# LEDboard_v0_2-R001.net
KiCad netlist of a schematic drawn in EAGLE
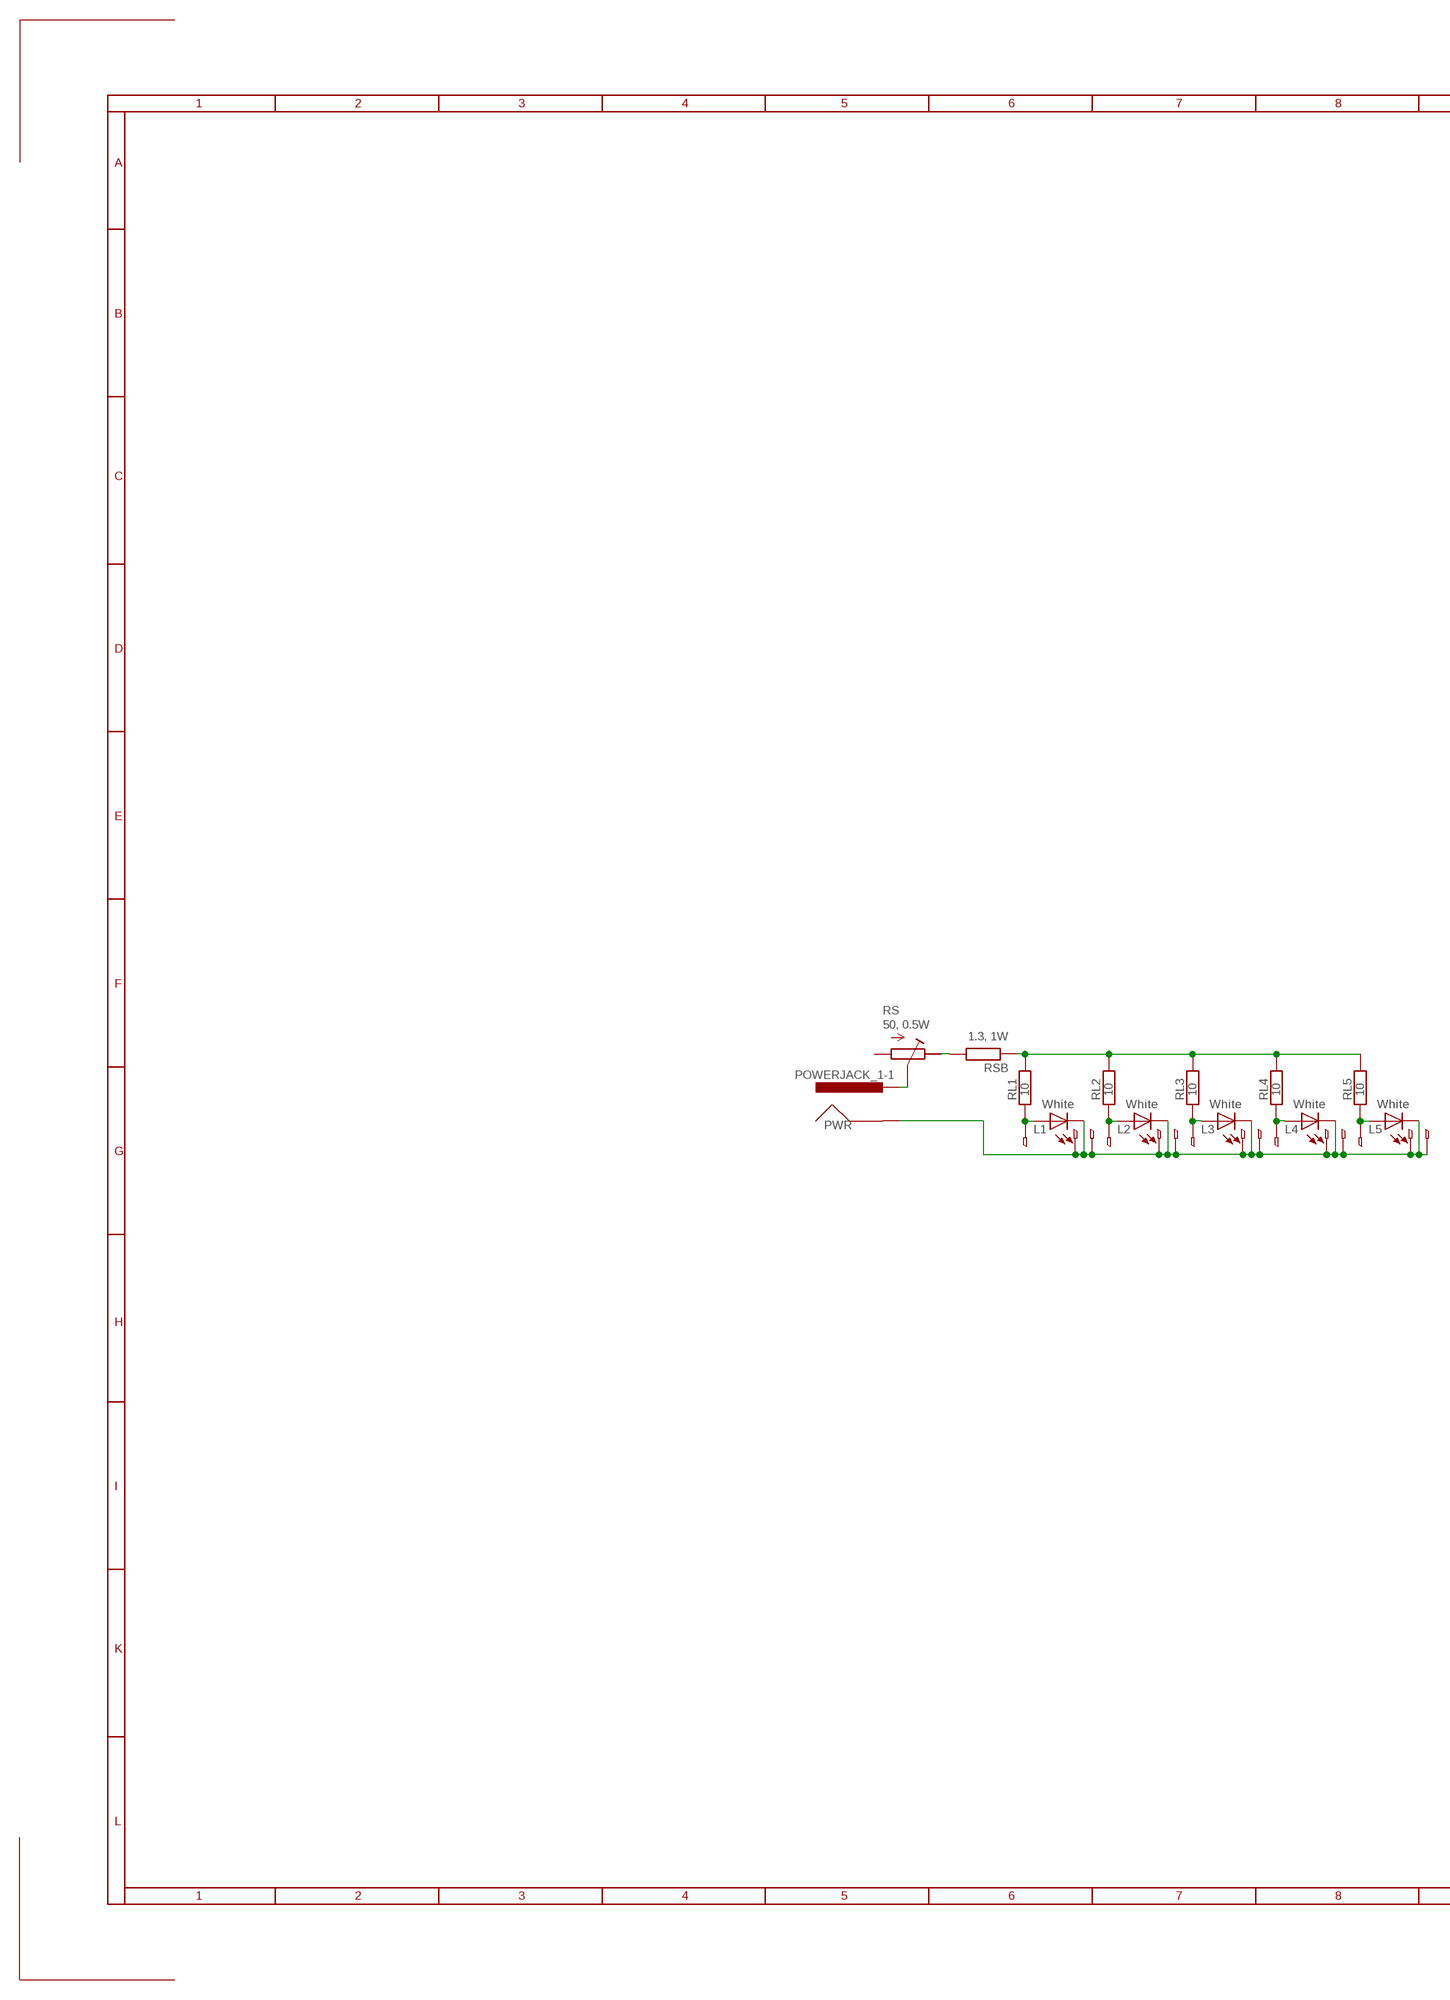
[diagram p0: schematic, sheet 1, part 1 of 2]
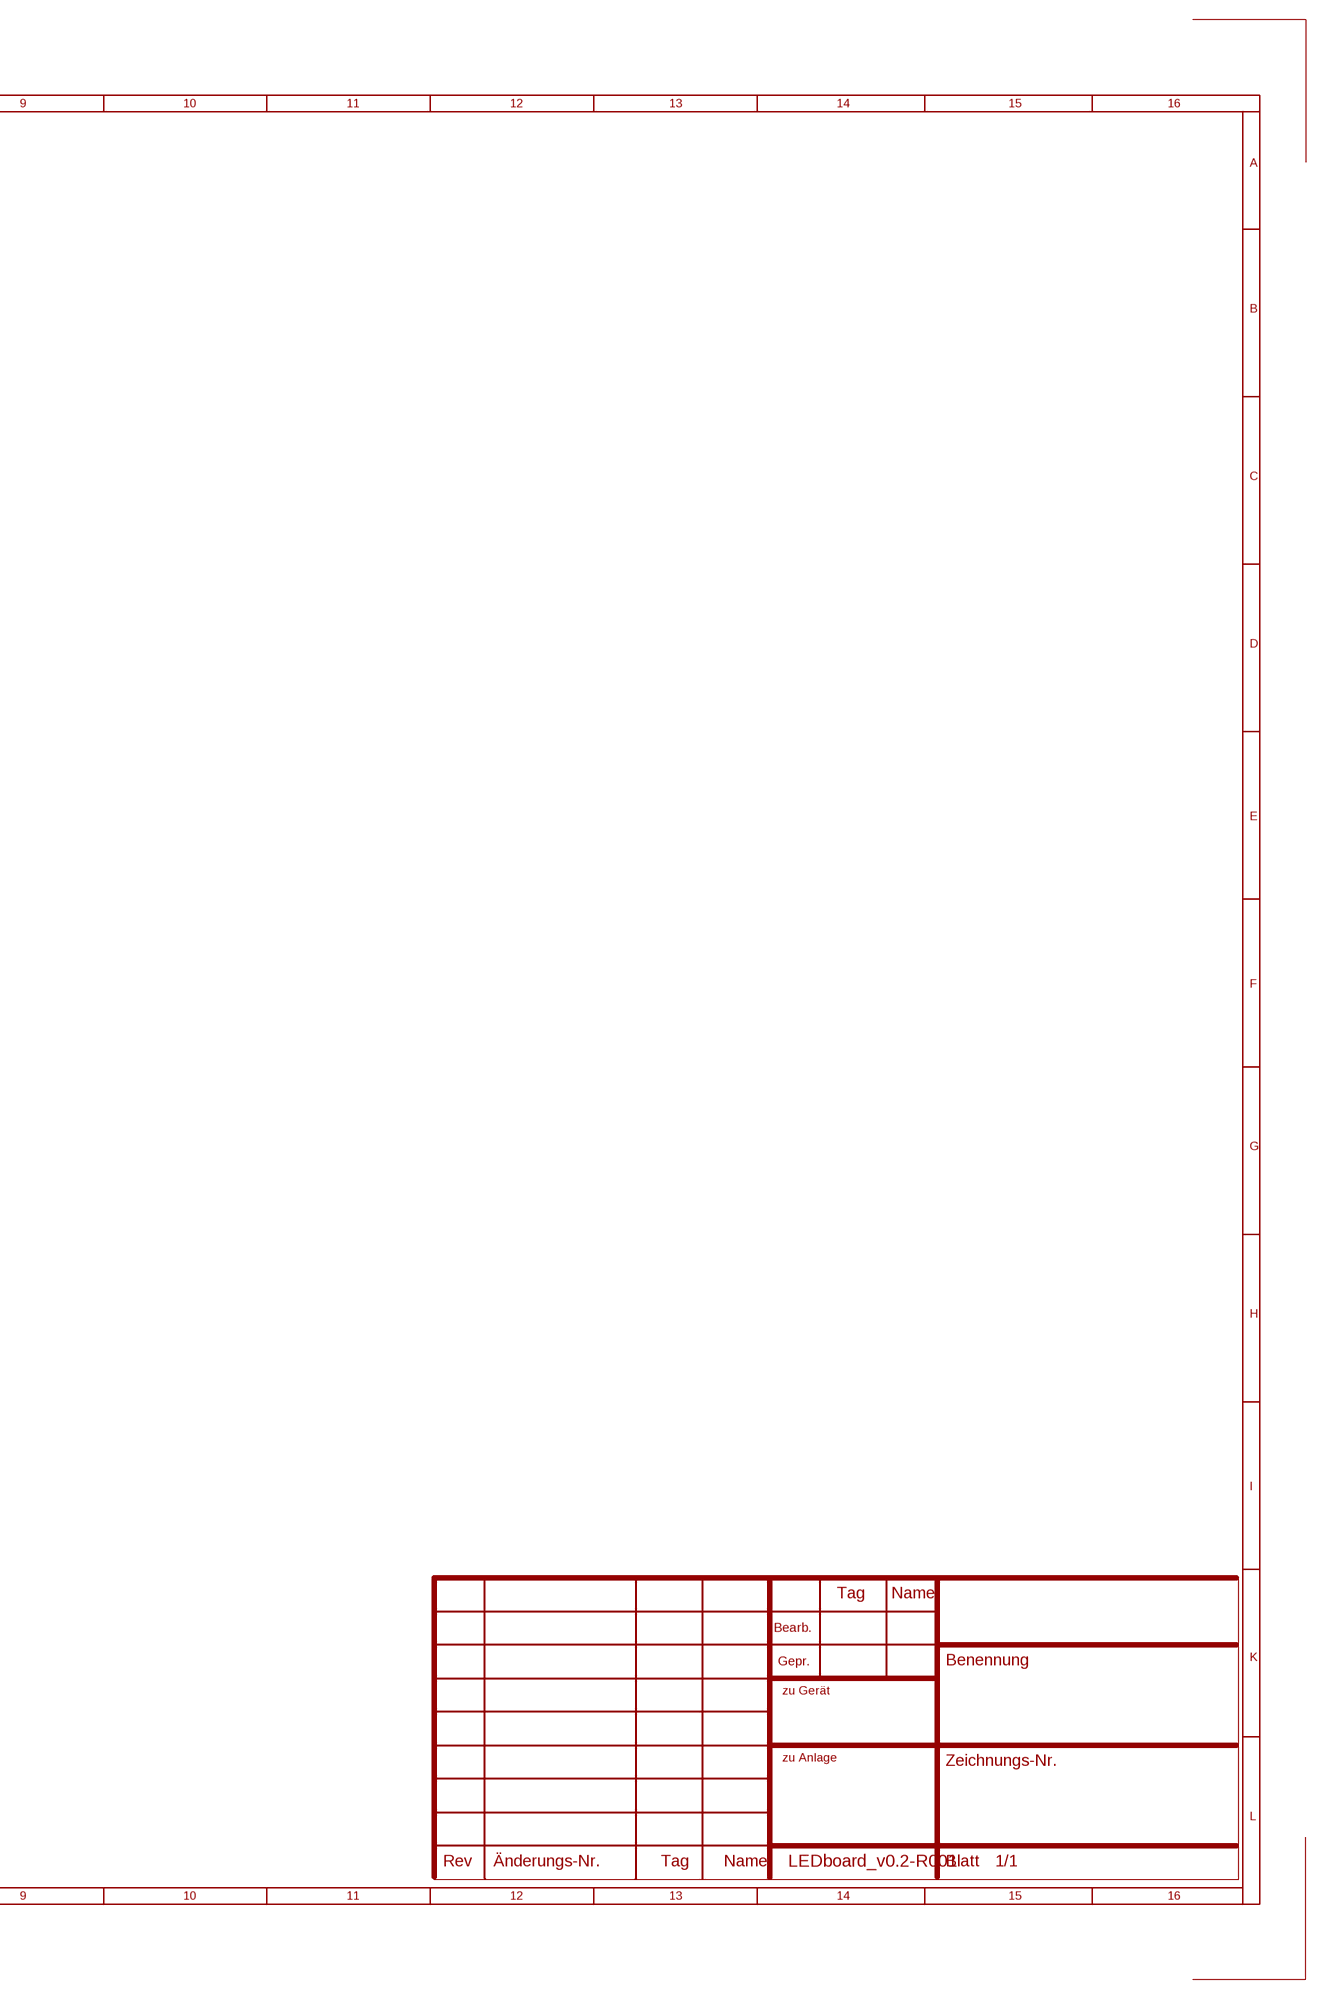
[diagram p1: schematic, sheet 1, part 2 of 2]

(export (version "E")
  (design (tool "Eeschema 10.0.6"))
  (components
    (comp (ref "L1")
      (value "White")
      (footprint "eagle-import:LED_LM561B")
      (libsource (lib "eagle-import") (part "LED_LM561B"))
    )
    (comp (ref "L2")
      (value "White")
      (footprint "eagle-import:LED_LM561B")
      (libsource (lib "eagle-import") (part "LED_LM561B"))
    )
    (comp (ref "L3")
      (value "White")
      (footprint "eagle-import:LED_LM561B")
      (libsource (lib "eagle-import") (part "LED_LM561B"))
    )
    (comp (ref "L4")
      (value "White")
      (footprint "eagle-import:LED_LM561B")
      (libsource (lib "eagle-import") (part "LED_LM561B"))
    )
    (comp (ref "L5")
      (value "White")
      (footprint "eagle-import:LED_LM561B")
      (libsource (lib "eagle-import") (part "LED_LM561B"))
    )
    (comp (ref "PWR")
      (value "POWERJACK_1-1")
      (footprint "eagle-import:MOLEX_KK4455-2P")
      (libsource (lib "eagle-import") (part "POWERJACK_1-1"))
    )
    (comp (ref "RL1")
      (value "10")
      (footprint "eagle-import:R0805")
      (libsource (lib "eagle-import") (part "R-EU_R0805"))
    )
    (comp (ref "RL2")
      (value "10")
      (footprint "eagle-import:R0805")
      (libsource (lib "eagle-import") (part "R-EU_R0805"))
    )
    (comp (ref "RL3")
      (value "10")
      (footprint "eagle-import:R0805")
      (libsource (lib "eagle-import") (part "R-EU_R0805"))
    )
    (comp (ref "RL4")
      (value "10")
      (footprint "eagle-import:R0805")
      (libsource (lib "eagle-import") (part "R-EU_R0805"))
    )
    (comp (ref "RL5")
      (value "10")
      (footprint "eagle-import:R0805")
      (libsource (lib "eagle-import") (part "R-EU_R0805"))
    )
    (comp (ref "RS")
      (value "50, 0.5W")
      (footprint "eagle-import:RTRIM3290H")
      (libsource (lib "eagle-import") (part "R-TRIMM3290H"))
    )
    (comp (ref "RSB")
      (value "1.3, 1W")
      (footprint "eagle-import:0207_2V")
      (libsource (lib "eagle-import") (part "R-EU_0207/2V"))
    )
  )
  (nets
    (net (code "1") (name "Net-(L1A-1)") (class "Default")
      (node (ref "L1") (pin "A1") (pinfunction "A_A1") (pintype "passive"))
      (node (ref "L1") (pin "A2") (pinfunction "1_A2") (pintype "passive"))
      (node (ref "RL1") (pin "1") (pinfunction "1_1") (pintype "passive"))
    )
    (net (code "2") (name "Net-(L1B-1)") (class "Default")
      (node (ref "L1") (pin "C1") (pinfunction "C_C1") (pintype "passive"))
      (node (ref "L1") (pin "C2") (pinfunction "1_C2") (pintype "passive"))
      (node (ref "L1") (pin "C3") (pinfunction "1_C3") (pintype "passive"))
      (node (ref "L2") (pin "C1") (pinfunction "C_C1") (pintype "passive"))
      (node (ref "L2") (pin "C2") (pinfunction "1_C2") (pintype "passive"))
      (node (ref "L2") (pin "C3") (pinfunction "1_C3") (pintype "passive"))
      (node (ref "L3") (pin "C1") (pinfunction "C_C1") (pintype "passive"))
      (node (ref "L3") (pin "C2") (pinfunction "1_C2") (pintype "passive"))
      (node (ref "L3") (pin "C3") (pinfunction "1_C3") (pintype "passive"))
      (node (ref "L4") (pin "C1") (pinfunction "C_C1") (pintype "passive"))
      (node (ref "L4") (pin "C2") (pinfunction "1_C2") (pintype "passive"))
      (node (ref "L4") (pin "C3") (pinfunction "1_C3") (pintype "passive"))
      (node (ref "L5") (pin "C1") (pinfunction "C_C1") (pintype "passive"))
      (node (ref "L5") (pin "C2") (pinfunction "1_C2") (pintype "passive"))
      (node (ref "L5") (pin "C3") (pinfunction "1_C3") (pintype "passive"))
      (node (ref "PWR") (pin "1") (pinfunction "GND_1") (pintype "power_in"))
    )
    (net (code "3") (name "Net-(L2A-1)") (class "Default")
      (node (ref "L2") (pin "A1") (pinfunction "A_A1") (pintype "passive"))
      (node (ref "L2") (pin "A2") (pinfunction "1_A2") (pintype "passive"))
      (node (ref "RL2") (pin "1") (pinfunction "1_1") (pintype "passive"))
    )
    (net (code "4") (name "Net-(L3A-1)") (class "Default")
      (node (ref "L3") (pin "A1") (pinfunction "A_A1") (pintype "passive"))
      (node (ref "L3") (pin "A2") (pinfunction "1_A2") (pintype "passive"))
      (node (ref "RL3") (pin "1") (pinfunction "1_1") (pintype "passive"))
    )
    (net (code "5") (name "Net-(L4A-1)") (class "Default")
      (node (ref "L4") (pin "A1") (pinfunction "A_A1") (pintype "passive"))
      (node (ref "L4") (pin "A2") (pinfunction "1_A2") (pintype "passive"))
      (node (ref "RL4") (pin "1") (pinfunction "1_1") (pintype "passive"))
    )
    (net (code "6") (name "Net-(L5A-1)") (class "Default")
      (node (ref "L5") (pin "A1") (pinfunction "A_A1") (pintype "passive"))
      (node (ref "L5") (pin "A2") (pinfunction "1_A2") (pintype "passive"))
      (node (ref "RL5") (pin "1") (pinfunction "1_1") (pintype "passive"))
    )
    (net (code "7") (name "Net-(PWR-PWR)") (class "Default")
      (node (ref "PWR") (pin "2") (pinfunction "PWR_2") (pintype "power_in"))
      (node (ref "RS") (pin "2") (pinfunction "S_2") (pintype "passive"))
    )
    (net (code "8") (name "Net-(RL1-Pad2)") (class "Default")
      (node (ref "RL1") (pin "2") (pinfunction "2_2") (pintype "passive"))
      (node (ref "RL2") (pin "2") (pinfunction "2_2") (pintype "passive"))
      (node (ref "RL3") (pin "2") (pinfunction "2_2") (pintype "passive"))
      (node (ref "RL4") (pin "2") (pinfunction "2_2") (pintype "passive"))
      (node (ref "RL5") (pin "2") (pinfunction "2_2") (pintype "passive"))
      (node (ref "RSB") (pin "1") (pinfunction "1_1") (pintype "passive"))
    )
    (net (code "9") (name "Net-(RS-A)") (class "Default")
      (node (ref "RS") (pin "3") (pinfunction "A_3") (pintype "passive"))
      (node (ref "RSB") (pin "2") (pinfunction "2_2") (pintype "passive"))
    )
    (net (code "10") (name "unconnected-(RS-E-Pad1)") (class "Default")
      (node (ref "RS") (pin "1") (pinfunction "E_1") (pintype "passive"))
    )
  )
)
